# USBtoATAPI.net
KiCad netlist of a schematic drawn in EAGLE
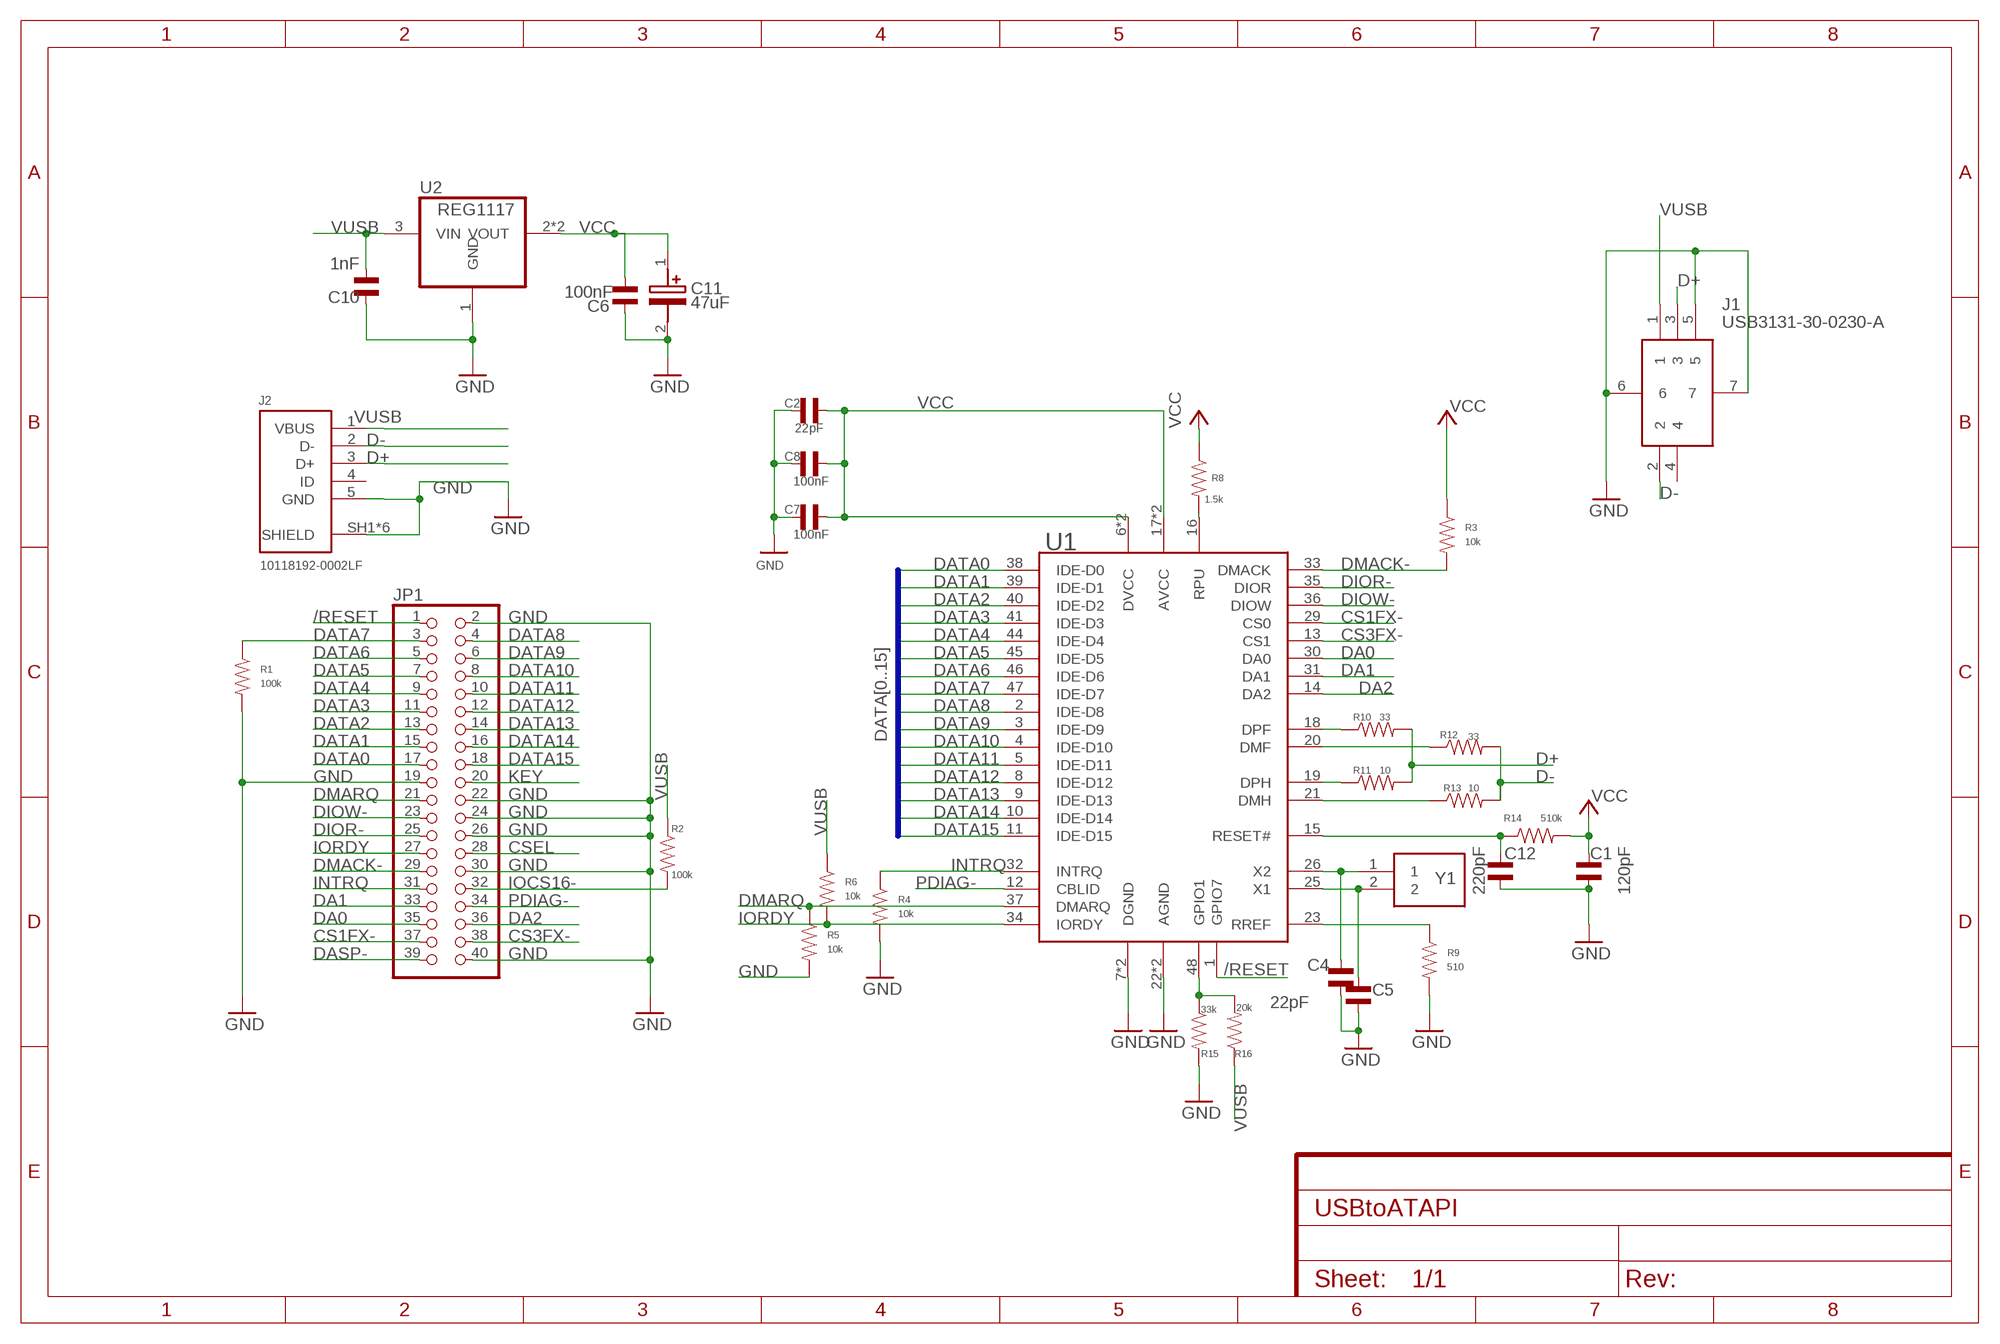
[diagram p0: schematic, sheet 1]

(export (version "E")
  (design (tool "Eeschema 10.0.6"))
  (components
    (comp (ref "C1")
      (value "120pF")
      (footprint "eagle-import:C0805")
      (libsource (lib "eagle-import") (part "CAPACITOR_NP_0805"))
    )
    (comp (ref "C2")
      (value "22pF")
      (footprint "eagle-import:C0805")
      (libsource (lib "eagle-import") (part "CAPACITOR_NP_0805"))
    )
    (comp (ref "C4")
      (value "22pF")
      (footprint "eagle-import:C0805")
      (libsource (lib "eagle-import") (part "CAPACITOR_NP_0805"))
    )
    (comp (ref "C5")
      (value "22pF")
      (footprint "eagle-import:C0805")
      (libsource (lib "eagle-import") (part "CAPACITOR_NP_0805"))
    )
    (comp (ref "C6")
      (value "100nF")
      (footprint "eagle-import:C0805")
      (libsource (lib "eagle-import") (part "CAPACITOR_NP_0805"))
    )
    (comp (ref "C7")
      (value "100nF")
      (footprint "eagle-import:C0805")
      (libsource (lib "eagle-import") (part "CAPACITOR_NP_0805"))
    )
    (comp (ref "C8")
      (value "100nF")
      (footprint "eagle-import:C0805")
      (libsource (lib "eagle-import") (part "CAPACITOR_NP_0805"))
    )
    (comp (ref "C10")
      (value "1nF")
      (footprint "eagle-import:C0805")
      (libsource (lib "eagle-import") (part "CAPACITOR_NP_0805"))
    )
    (comp (ref "C11")
      (value "47uF")
      (footprint "eagle-import:CAPAE430X550N")
      (fields
        (field (name "MANUFACTURER_PART_NUMBER") "UWR0J470MCL1GB")
        (field (name "MOUSER_PART_NUMBER") "647-UWR0J470MCL1GB")
      )
      (libsource (lib "eagle-import") (part "UWR0J470MCL1GB"))
    )
    (comp (ref "C12")
      (value "220pF")
      (footprint "eagle-import:C0805")
      (libsource (lib "eagle-import") (part "CAPACITOR_NP_0805"))
    )
    (comp (ref "J1")
      (value "USB3131-30-0230-A")
      (footprint "eagle-import:USB3131300230A")
      (fields (field (name "MOUSER_PART_NUMBER") "640-USB3131300230A"))
      (libsource (lib "eagle-import") (part "USB3131-30-0230-A"))
    )
    (comp (ref "J2")
      (value "10118192-0002LF")
      (footprint "eagle-import:10118192-0002LF")
      (fields
        (field (name "DIGIKEY_PARTNO") "609-5379-2-ND")
        (field (name "MANUFACTURER") "Amphenol ICC (FCI)")
        (field (name "CREATED_BY") "PCBLayout.com")
      )
      (libsource (lib "eagle-import") (part "10118192-0002LF"))
    )
    (comp (ref "JP1")
      (value "PINHD-2X20")
      (footprint "eagle-import:2X20")
      (libsource (lib "eagle-import") (part "PINHD-2X20"))
    )
    (comp (ref "R1")
      (value "100k")
      (footprint "eagle-import:R0805")
      (libsource (lib "eagle-import") (part "RESISTOR_0805"))
    )
    (comp (ref "R2")
      (value "100k")
      (footprint "eagle-import:R0805")
      (libsource (lib "eagle-import") (part "RESISTOR_0805"))
    )
    (comp (ref "R3")
      (value "10k")
      (footprint "eagle-import:R0805")
      (libsource (lib "eagle-import") (part "RESISTOR_0805"))
    )
    (comp (ref "R4")
      (value "10k")
      (footprint "eagle-import:R0805")
      (libsource (lib "eagle-import") (part "RESISTOR_0805"))
    )
    (comp (ref "R5")
      (value "10k")
      (footprint "eagle-import:R0805")
      (libsource (lib "eagle-import") (part "RESISTOR_0805"))
    )
    (comp (ref "R6")
      (value "10k")
      (footprint "eagle-import:R0805")
      (libsource (lib "eagle-import") (part "RESISTOR_0805"))
    )
    (comp (ref "R8")
      (value "1.5k")
      (footprint "eagle-import:R0805")
      (libsource (lib "eagle-import") (part "RESISTOR_0805"))
    )
    (comp (ref "R9")
      (value "510")
      (footprint "eagle-import:R0805")
      (libsource (lib "eagle-import") (part "RESISTOR_0805"))
    )
    (comp (ref "R10")
      (value "33")
      (footprint "eagle-import:R0805")
      (libsource (lib "eagle-import") (part "RESISTOR_0805"))
    )
    (comp (ref "R11")
      (value "10")
      (footprint "eagle-import:R0805")
      (libsource (lib "eagle-import") (part "RESISTOR_0805"))
    )
    (comp (ref "R12")
      (value "33")
      (footprint "eagle-import:R0805")
      (libsource (lib "eagle-import") (part "RESISTOR_0805"))
    )
    (comp (ref "R13")
      (value "10")
      (footprint "eagle-import:R0805")
      (libsource (lib "eagle-import") (part "RESISTOR_0805"))
    )
    (comp (ref "R14")
      (value "510k")
      (footprint "eagle-import:R0805")
      (libsource (lib "eagle-import") (part "RESISTOR_0805"))
    )
    (comp (ref "R15")
      (value "33k")
      (footprint "eagle-import:R0805")
      (libsource (lib "eagle-import") (part "RESISTOR_0805"))
    )
    (comp (ref "R16")
      (value "20k")
      (footprint "eagle-import:R0805")
      (libsource (lib "eagle-import") (part "RESISTOR_0805"))
    )
    (comp (ref "U1")
      (value "GL811E")
      (footprint "eagle-import:LQFP-48")
      (libsource (lib "eagle-import") (part "GL811E"))
    )
    (comp (ref "U2")
      (value "REG1117")
      (footprint "eagle-import:SOT223")
      (libsource (lib "eagle-import") (part "REG1117"))
    )
    (comp (ref "Y1")
      (value "445C33C12M00000")
      (footprint "eagle-import:445C33C12M00000")
      (fields (field (name "MOUSER_PART_NUMBER") "774-445C33C12M00000"))
      (libsource (lib "eagle-import") (part "445C33C12M00000"))
    )
  )
  (nets
    (net (code "1") (name "/CS1FX-") (class "Default")
      (node (ref "JP1") (pin "37") (pinfunction "37_37") (pintype "passive"))
      (node (ref "U1") (pin "29") (pinfunction "CS0_29") (pintype "bidirectional"))
    )
    (net (code "2") (name "/CS3FX-") (class "Default")
      (node (ref "JP1") (pin "38") (pinfunction "38_38") (pintype "passive"))
      (node (ref "U1") (pin "13") (pinfunction "CS1_13") (pintype "bidirectional"))
    )
    (net (code "3") (name "/CSEL") (class "Default")
      (node (ref "JP1") (pin "28") (pinfunction "28_28") (pintype "passive"))
    )
    (net (code "4") (name "/D+") (class "Default")
      (node (ref "J1") (pin "3") (pinfunction "3_3") (pintype "bidirectional"))
      (node (ref "J2") (pin "3") (pinfunction "D+_3") (pintype "passive"))
      (node (ref "R10") (pin "P$2") (pinfunction "P$2_P$2") (pintype "passive"))
      (node (ref "R11") (pin "P$2") (pinfunction "P$2_P$2") (pintype "passive"))
    )
    (net (code "5") (name "/D-") (class "Default")
      (node (ref "J1") (pin "2") (pinfunction "2_2") (pintype "bidirectional"))
      (node (ref "J2") (pin "2") (pinfunction "D-_2") (pintype "passive"))
      (node (ref "R12") (pin "P$2") (pinfunction "P$2_P$2") (pintype "passive"))
      (node (ref "R13") (pin "P$2") (pinfunction "P$2_P$2") (pintype "passive"))
    )
    (net (code "6") (name "/DA0") (class "Default")
      (node (ref "JP1") (pin "35") (pinfunction "35_35") (pintype "passive"))
      (node (ref "U1") (pin "30") (pinfunction "DA0_30") (pintype "bidirectional"))
    )
    (net (code "7") (name "/DA1") (class "Default")
      (node (ref "JP1") (pin "33") (pinfunction "33_33") (pintype "passive"))
      (node (ref "U1") (pin "31") (pinfunction "DA1_31") (pintype "bidirectional"))
    )
    (net (code "8") (name "/DA2") (class "Default")
      (node (ref "JP1") (pin "36") (pinfunction "36_36") (pintype "passive"))
      (node (ref "U1") (pin "14") (pinfunction "DA2_14") (pintype "bidirectional"))
    )
    (net (code "9") (name "/DASP-") (class "Default")
      (node (ref "JP1") (pin "39") (pinfunction "39_39") (pintype "passive"))
    )
    (net (code "10") (name "/DATA0") (class "Default")
      (node (ref "JP1") (pin "17") (pinfunction "17_17") (pintype "passive"))
      (node (ref "U1") (pin "38") (pinfunction "IDE-D0_38") (pintype "bidirectional"))
    )
    (net (code "11") (name "/DATA1") (class "Default")
      (node (ref "JP1") (pin "15") (pinfunction "15_15") (pintype "passive"))
      (node (ref "U1") (pin "39") (pinfunction "IDE-D1_39") (pintype "bidirectional"))
    )
    (net (code "12") (name "/DATA2") (class "Default")
      (node (ref "JP1") (pin "13") (pinfunction "13_13") (pintype "passive"))
      (node (ref "U1") (pin "40") (pinfunction "IDE-D2_40") (pintype "bidirectional"))
    )
    (net (code "13") (name "/DATA3") (class "Default")
      (node (ref "JP1") (pin "11") (pinfunction "11_11") (pintype "passive"))
      (node (ref "U1") (pin "41") (pinfunction "IDE-D3_41") (pintype "bidirectional"))
    )
    (net (code "14") (name "/DATA4") (class "Default")
      (node (ref "JP1") (pin "9") (pinfunction "9_9") (pintype "passive"))
      (node (ref "U1") (pin "44") (pinfunction "IDE-D4_44") (pintype "bidirectional"))
    )
    (net (code "15") (name "/DATA5") (class "Default")
      (node (ref "JP1") (pin "7") (pinfunction "7_7") (pintype "passive"))
      (node (ref "U1") (pin "45") (pinfunction "IDE-D5_45") (pintype "bidirectional"))
    )
    (net (code "16") (name "/DATA6") (class "Default")
      (node (ref "JP1") (pin "5") (pinfunction "5_5") (pintype "passive"))
      (node (ref "U1") (pin "46") (pinfunction "IDE-D6_46") (pintype "bidirectional"))
    )
    (net (code "17") (name "/DATA7") (class "Default")
      (node (ref "JP1") (pin "3") (pinfunction "3_3") (pintype "passive"))
      (node (ref "R1") (pin "P$1") (pinfunction "P$1_P$1") (pintype "passive"))
      (node (ref "U1") (pin "47") (pinfunction "IDE-D7_47") (pintype "bidirectional"))
    )
    (net (code "18") (name "/DATA8") (class "Default")
      (node (ref "JP1") (pin "4") (pinfunction "4_4") (pintype "passive"))
      (node (ref "U1") (pin "2") (pinfunction "IDE-D8_2") (pintype "bidirectional"))
    )
    (net (code "19") (name "/DATA9") (class "Default")
      (node (ref "JP1") (pin "6") (pinfunction "6_6") (pintype "passive"))
      (node (ref "U1") (pin "3") (pinfunction "IDE-D9_3") (pintype "bidirectional"))
    )
    (net (code "20") (name "/DATA10") (class "Default")
      (node (ref "JP1") (pin "8") (pinfunction "8_8") (pintype "passive"))
      (node (ref "U1") (pin "4") (pinfunction "IDE-D10_4") (pintype "bidirectional"))
    )
    (net (code "21") (name "/DATA11") (class "Default")
      (node (ref "JP1") (pin "10") (pinfunction "10_10") (pintype "passive"))
      (node (ref "U1") (pin "5") (pinfunction "IDE-D11_5") (pintype "bidirectional"))
    )
    (net (code "22") (name "/DATA12") (class "Default")
      (node (ref "JP1") (pin "12") (pinfunction "12_12") (pintype "passive"))
      (node (ref "U1") (pin "8") (pinfunction "IDE-D12_8") (pintype "bidirectional"))
    )
    (net (code "23") (name "/DATA13") (class "Default")
      (node (ref "JP1") (pin "14") (pinfunction "14_14") (pintype "passive"))
      (node (ref "U1") (pin "9") (pinfunction "IDE-D13_9") (pintype "bidirectional"))
    )
    (net (code "24") (name "/DATA14") (class "Default")
      (node (ref "JP1") (pin "16") (pinfunction "16_16") (pintype "passive"))
      (node (ref "U1") (pin "10") (pinfunction "IDE-D14_10") (pintype "bidirectional"))
    )
    (net (code "25") (name "/DATA15") (class "Default")
      (node (ref "JP1") (pin "18") (pinfunction "18_18") (pintype "passive"))
      (node (ref "U1") (pin "11") (pinfunction "IDE-D15_11") (pintype "bidirectional"))
    )
    (net (code "27") (name "/DIOR-") (class "Default")
      (node (ref "JP1") (pin "25") (pinfunction "25_25") (pintype "passive"))
      (node (ref "U1") (pin "35") (pinfunction "DIOR_35") (pintype "bidirectional"))
    )
    (net (code "28") (name "/DIOW-") (class "Default")
      (node (ref "JP1") (pin "23") (pinfunction "23_23") (pintype "passive"))
      (node (ref "U1") (pin "36") (pinfunction "DIOW_36") (pintype "bidirectional"))
    )
    (net (code "29") (name "/DMACK-") (class "Default")
      (node (ref "JP1") (pin "29") (pinfunction "29_29") (pintype "passive"))
      (node (ref "R3") (pin "P$2") (pinfunction "P$2_P$2") (pintype "passive"))
      (node (ref "U1") (pin "33") (pinfunction "DMACK_33") (pintype "bidirectional"))
    )
    (net (code "30") (name "/DMARQ") (class "Default")
      (node (ref "JP1") (pin "21") (pinfunction "21_21") (pintype "passive"))
      (node (ref "R5") (pin "P$1") (pinfunction "P$1_P$1") (pintype "passive"))
      (node (ref "U1") (pin "37") (pinfunction "DMARQ_37") (pintype "bidirectional"))
    )
    (net (code "31") (name "/INTRQ") (class "Default")
      (node (ref "JP1") (pin "31") (pinfunction "31_31") (pintype "passive"))
      (node (ref "R4") (pin "P$1") (pinfunction "P$1_P$1") (pintype "passive"))
      (node (ref "U1") (pin "32") (pinfunction "INTRQ_32") (pintype "bidirectional"))
    )
    (net (code "32") (name "/IOCS16-") (class "Default")
      (node (ref "JP1") (pin "32") (pinfunction "32_32") (pintype "passive"))
      (node (ref "R2") (pin "P$2") (pinfunction "P$2_P$2") (pintype "passive"))
    )
    (net (code "33") (name "/IORDY") (class "Default")
      (node (ref "JP1") (pin "27") (pinfunction "27_27") (pintype "passive"))
      (node (ref "R6") (pin "P$2") (pinfunction "P$2_P$2") (pintype "passive"))
      (node (ref "U1") (pin "34") (pinfunction "IORDY_34") (pintype "bidirectional"))
    )
    (net (code "34") (name "/KEY") (class "Default")
      (node (ref "JP1") (pin "20") (pinfunction "20_20") (pintype "passive"))
    )
    (net (code "35") (name "/PDIAG-") (class "Default")
      (node (ref "JP1") (pin "34") (pinfunction "34_34") (pintype "passive"))
      (node (ref "U1") (pin "12") (pinfunction "CBLID_12") (pintype "bidirectional"))
    )
    (net (code "36") (name "/VUSB") (class "Default")
      (node (ref "C10") (pin "P$2") (pinfunction "P$2_P$2") (pintype "passive"))
      (node (ref "J1") (pin "1") (pinfunction "1_1") (pintype "bidirectional"))
      (node (ref "J2") (pin "1") (pinfunction "VBUS_1") (pintype "passive"))
      (node (ref "R16") (pin "P$1") (pinfunction "P$1_P$1") (pintype "passive"))
      (node (ref "R2") (pin "P$1") (pinfunction "P$1_P$1") (pintype "passive"))
      (node (ref "R6") (pin "P$1") (pinfunction "P$1_P$1") (pintype "passive"))
      (node (ref "U2") (pin "3") (pinfunction "VIN_3") (pintype "input"))
    )
    (net (code "37") (name "/{slash}RESET") (class "Default")
      (node (ref "JP1") (pin "1") (pinfunction "1_1") (pintype "passive"))
      (node (ref "U1") (pin "1") (pinfunction "GPIO7_1") (pintype "bidirectional"))
    )
    (net (code "38") (name "GND") (class "Default")
      (node (ref "C1") (pin "P$1") (pinfunction "P$1_P$1") (pintype "passive"))
      (node (ref "C10") (pin "P$1") (pinfunction "P$1_P$1") (pintype "passive"))
      (node (ref "C11") (pin "2") (pinfunction "-_2") (pintype "bidirectional"))
      (node (ref "C12") (pin "P$1") (pinfunction "P$1_P$1") (pintype "passive"))
      (node (ref "C2") (pin "P$1") (pinfunction "P$1_P$1") (pintype "passive"))
      (node (ref "C4") (pin "P$2") (pinfunction "P$2_P$2") (pintype "passive"))
      (node (ref "C5") (pin "P$1") (pinfunction "P$1_P$1") (pintype "passive"))
      (node (ref "C6") (pin "P$1") (pinfunction "P$1_P$1") (pintype "passive"))
      (node (ref "C7") (pin "P$2") (pinfunction "P$2_P$2") (pintype "passive"))
      (node (ref "C8") (pin "P$2") (pinfunction "P$2_P$2") (pintype "passive"))
      (node (ref "J1") (pin "5") (pinfunction "5_5") (pintype "bidirectional"))
      (node (ref "J1") (pin "6") (pinfunction "6_6") (pintype "bidirectional"))
      (node (ref "J1") (pin "7") (pinfunction "7_7") (pintype "bidirectional"))
      (node (ref "J2") (pin "5") (pinfunction "GND_5") (pintype "passive"))
      (node (ref "J2") (pin "SH1") (pinfunction "SHIELD_SH1") (pintype "power_in"))
      (node (ref "J2") (pin "SH2") (pinfunction "SHIELD_SH2") (pintype "power_in"))
      (node (ref "J2") (pin "SH3") (pinfunction "SHIELD_SH3") (pintype "power_in"))
      (node (ref "J2") (pin "SH4") (pinfunction "SHIELD_SH4") (pintype "power_in"))
      (node (ref "J2") (pin "SH5") (pinfunction "SHIELD_SH5") (pintype "power_in"))
      (node (ref "J2") (pin "SH6") (pinfunction "SHIELD_SH6") (pintype "power_in"))
      (node (ref "JP1") (pin "19") (pinfunction "19_19") (pintype "passive"))
      (node (ref "JP1") (pin "2") (pinfunction "2_2") (pintype "passive"))
      (node (ref "JP1") (pin "22") (pinfunction "22_22") (pintype "passive"))
      (node (ref "JP1") (pin "24") (pinfunction "24_24") (pintype "passive"))
      (node (ref "JP1") (pin "26") (pinfunction "26_26") (pintype "passive"))
      (node (ref "JP1") (pin "30") (pinfunction "30_30") (pintype "passive"))
      (node (ref "JP1") (pin "40") (pinfunction "40_40") (pintype "passive"))
      (node (ref "R1") (pin "P$2") (pinfunction "P$2_P$2") (pintype "passive"))
      (node (ref "R15") (pin "P$2") (pinfunction "P$2_P$2") (pintype "passive"))
      (node (ref "R4") (pin "P$2") (pinfunction "P$2_P$2") (pintype "passive"))
      (node (ref "R5") (pin "P$2") (pinfunction "P$2_P$2") (pintype "passive"))
      (node (ref "R9") (pin "P$2") (pinfunction "P$2_P$2") (pintype "passive"))
      (node (ref "U1") (pin "22") (pinfunction "AGND_22") (pintype "bidirectional"))
      (node (ref "U1") (pin "27") (pinfunction "AGND_27") (pintype "bidirectional"))
      (node (ref "U1") (pin "42") (pinfunction "DGND_42") (pintype "bidirectional"))
      (node (ref "U1") (pin "7") (pinfunction "DGND_7") (pintype "bidirectional"))
      (node (ref "U2") (pin "1") (pinfunction "GND_1") (pintype "power_in"))
    )
    (net (code "39") (name "Net-(U1-DMF)") (class "Default")
      (node (ref "R12") (pin "P$1") (pinfunction "P$1_P$1") (pintype "passive"))
      (node (ref "U1") (pin "20") (pinfunction "DMF_20") (pintype "bidirectional"))
    )
    (net (code "40") (name "Net-(U1-DMH)") (class "Default")
      (node (ref "R13") (pin "P$1") (pinfunction "P$1_P$1") (pintype "passive"))
      (node (ref "U1") (pin "21") (pinfunction "DMH_21") (pintype "bidirectional"))
    )
    (net (code "41") (name "Net-(U1-DPF)") (class "Default")
      (node (ref "R10") (pin "P$1") (pinfunction "P$1_P$1") (pintype "passive"))
      (node (ref "U1") (pin "18") (pinfunction "DPF_18") (pintype "bidirectional"))
    )
    (net (code "42") (name "Net-(U1-DPH)") (class "Default")
      (node (ref "R11") (pin "P$1") (pinfunction "P$1_P$1") (pintype "passive"))
      (node (ref "U1") (pin "19") (pinfunction "DPH_19") (pintype "bidirectional"))
    )
    (net (code "43") (name "Net-(U1-GPIO1)") (class "Default")
      (node (ref "R15") (pin "P$1") (pinfunction "P$1_P$1") (pintype "passive"))
      (node (ref "R16") (pin "P$2") (pinfunction "P$2_P$2") (pintype "passive"))
      (node (ref "U1") (pin "48") (pinfunction "GPIO1_48") (pintype "bidirectional"))
    )
    (net (code "44") (name "Net-(U1-RESET#)") (class "Default")
      (node (ref "C12") (pin "P$2") (pinfunction "P$2_P$2") (pintype "passive"))
      (node (ref "R14") (pin "P$1") (pinfunction "P$1_P$1") (pintype "passive"))
      (node (ref "U1") (pin "15") (pinfunction "RESET#_15") (pintype "bidirectional"))
    )
    (net (code "45") (name "Net-(U1-RPU)") (class "Default")
      (node (ref "R8") (pin "P$2") (pinfunction "P$2_P$2") (pintype "passive"))
      (node (ref "U1") (pin "16") (pinfunction "RPU_16") (pintype "bidirectional"))
    )
    (net (code "46") (name "Net-(U1-RREF)") (class "Default")
      (node (ref "R9") (pin "P$1") (pinfunction "P$1_P$1") (pintype "passive"))
      (node (ref "U1") (pin "23") (pinfunction "RREF_23") (pintype "bidirectional"))
    )
    (net (code "47") (name "Net-(U1-X1)") (class "Default")
      (node (ref "C5") (pin "P$2") (pinfunction "P$2_P$2") (pintype "passive"))
      (node (ref "U1") (pin "25") (pinfunction "X1_25") (pintype "bidirectional"))
      (node (ref "Y1") (pin "2") (pinfunction "2_2") (pintype "bidirectional"))
    )
    (net (code "48") (name "Net-(U1-X2)") (class "Default")
      (node (ref "C4") (pin "P$1") (pinfunction "P$1_P$1") (pintype "passive"))
      (node (ref "U1") (pin "26") (pinfunction "X2_26") (pintype "bidirectional"))
      (node (ref "Y1") (pin "1") (pinfunction "1_1") (pintype "bidirectional"))
    )
    (net (code "49") (name "VCC") (class "Default")
      (node (ref "C1") (pin "P$2") (pinfunction "P$2_P$2") (pintype "passive"))
      (node (ref "C11") (pin "1") (pinfunction "+_1") (pintype "bidirectional"))
      (node (ref "C2") (pin "P$2") (pinfunction "P$2_P$2") (pintype "passive"))
      (node (ref "C6") (pin "P$2") (pinfunction "P$2_P$2") (pintype "passive"))
      (node (ref "C7") (pin "P$1") (pinfunction "P$1_P$1") (pintype "passive"))
      (node (ref "C8") (pin "P$1") (pinfunction "P$1_P$1") (pintype "passive"))
      (node (ref "R14") (pin "P$2") (pinfunction "P$2_P$2") (pintype "passive"))
      (node (ref "R3") (pin "P$1") (pinfunction "P$1_P$1") (pintype "passive"))
      (node (ref "R8") (pin "P$1") (pinfunction "P$1_P$1") (pintype "passive"))
      (node (ref "U1") (pin "17") (pinfunction "AVCC_17") (pintype "bidirectional"))
      (node (ref "U1") (pin "24") (pinfunction "AVCC_24") (pintype "bidirectional"))
      (node (ref "U1") (pin "43") (pinfunction "DVCC_43") (pintype "bidirectional"))
      (node (ref "U1") (pin "6") (pinfunction "DVCC_6") (pintype "bidirectional"))
      (node (ref "U2") (pin "2") (pinfunction "VOUT_2") (pintype "output"))
      (node (ref "U2") (pin "4") (pinfunction "VOUT_4") (pintype "output"))
    )
    (net (code "50") (name "unconnected-(J1-Pad4)") (class "Default")
      (node (ref "J1") (pin "4") (pinfunction "4_4") (pintype "bidirectional"))
    )
    (net (code "51") (name "unconnected-(J2-ID-Pad4)") (class "Default")
      (node (ref "J2") (pin "4") (pinfunction "ID_4") (pintype "passive"))
    )
  )
)
